# Integrators_Soldier.net
KiCad netlist of a schematic drawn in Altium Designer
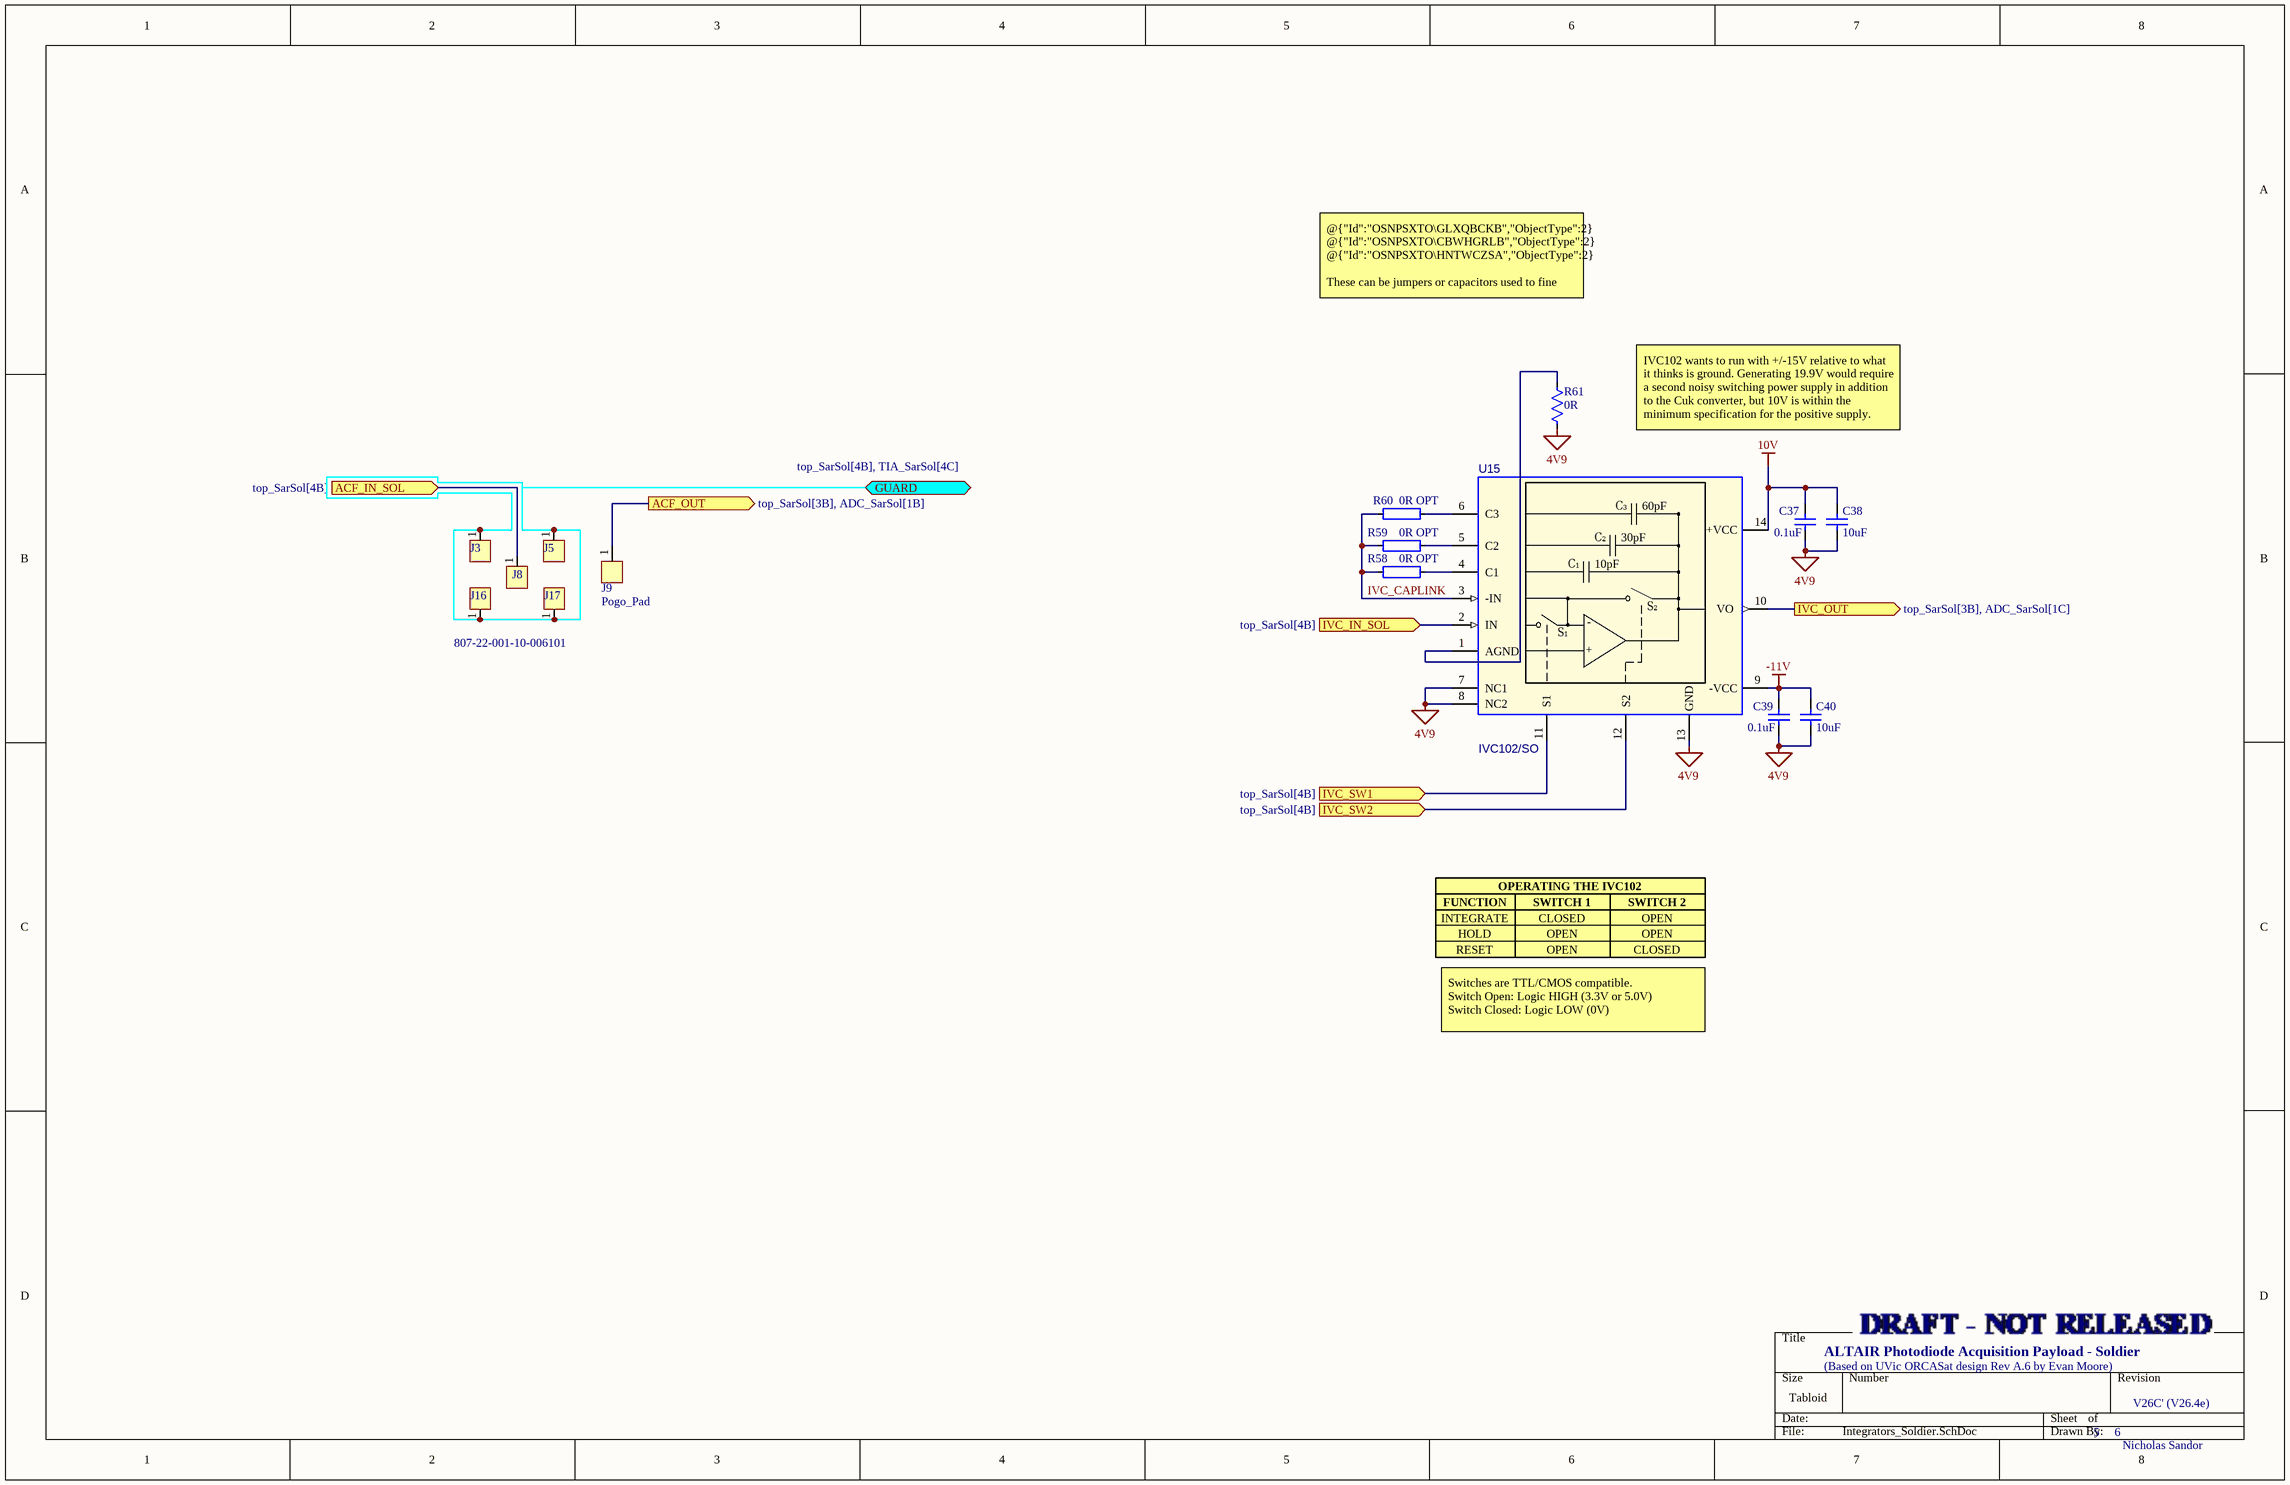
[diagram p0: Integrators_Soldier.SchDoc]

(export (version "E")
  (design (tool "Eeschema 10.0.6"))
  (components
    (comp (ref "C37")
      (value "0.1uF")
      (footprint "CAP 0603 NON-IPC KEMET X7R")
      (description "Kemet C0603C104K5RACAUTO - Cap Ceramic 0.1uF 50V X7R 10% 0603 125C Paper T/R")
      (fields (field (name "MF") "Kemet") (field (name "MP") "C0603C104K5RACAUTO"))
      (libsource (lib "ALTAIR_PD_Capacitors") (part "CAP"))
    )
    (comp (ref "C38")
      (value "10uF")
      (footprint "CAP 0805 IPC MID DENSITY")
      (description "Murata GRM21BR61E106KA73L - Cap Ceramic 10uF 10% 25V X5R 0805")
      (fields (field (name "MF") "Murata") (field (name "MP") "GRM21BR61E106KA73L"))
      (libsource (lib "ALTAIR_PD_Capacitors") (part "CAP"))
    )
    (comp (ref "C39")
      (value "0.1uF")
      (footprint "CAP 0603 NON-IPC KEMET X7R")
      (description "Kemet C0603C104K5RACAUTO - Cap Ceramic 0.1uF 50V X7R 10% 0603 125C Paper T/R")
      (fields (field (name "MF") "Kemet") (field (name "MP") "C0603C104K5RACAUTO"))
      (libsource (lib "ALTAIR_PD_Capacitors") (part "CAP"))
    )
    (comp (ref "C40")
      (value "10uF")
      (footprint "CAP 0805 IPC MID DENSITY")
      (description "Murata GRM21BR61E106KA73L - Cap Ceramic 10uF 10% 25V X5R 0805")
      (fields (field (name "MF") "Murata") (field (name "MP") "GRM21BR61E106KA73L"))
      (libsource (lib "ALTAIR_PD_Capacitors") (part "CAP"))
    )
    (comp (ref "J3")
      (value "807-22-001-10-006101")
      (footprint "POGO PIN 807-22-001-10-006101")
      (description "Mill-Max Individual Insulated Pin 5.99mm Initial Height")
      (fields (field (name "MF") "Mill-Max"))
      (libsource (lib "ALTAIR_PD_Pogo") (part "807-22-001-10-006101"))
    )
    (comp (ref "J5")
      (value "807-22-001-10-006101")
      (footprint "POGO PIN 807-22-001-10-006101")
      (description "Mill-Max Individual Insulated Pin 5.99mm Initial Height")
      (fields (field (name "MF") "Mill-Max"))
      (libsource (lib "ALTAIR_PD_Pogo") (part "807-22-001-10-006101"))
    )
    (comp (ref "J8")
      (value "807-22-001-10-006101")
      (footprint "POGO PIN 807-22-001-10-006101")
      (description "Mill-Max Individual Insulated Pin 5.99mm Initial Height")
      (fields (field (name "MF") "Mill-Max"))
      (libsource (lib "ALTAIR_PD_Pogo") (part "807-22-001-10-006101"))
    )
    (comp (ref "J9")
      (value "Pogo_Pad")
      (footprint "POGO PAD SOLDIER")
      (description "Pad for Pogo Pin without Guard")
      (libsource (lib "ALTAIR_PD_Pogo") (part "Pogo_Pad_NoGuard"))
    )
    (comp (ref "J16")
      (value "807-22-001-10-006101")
      (footprint "POGO PIN 807-22-001-10-006101")
      (description "Mill-Max Individual Insulated Pin 5.99mm Initial Height")
      (fields (field (name "MF") "Mill-Max"))
      (libsource (lib "") (part "807-22-001-10-006101_1"))
    )
    (comp (ref "J17")
      (value "807-22-001-10-006101")
      (footprint "POGO PIN 807-22-001-10-006101")
      (description "Mill-Max Individual Insulated Pin 5.99mm Initial Height")
      (fields (field (name "MF") "Mill-Max"))
      (libsource (lib "") (part "807-22-001-10-006101_1"))
    )
    (comp (ref "R58")
      (value "0R OPT")
      (footprint "RES 0402 IPC LOW DENSITY")
      (description "Yageo RC0402JR-070RL - Res 0 Ohms 1/16W SMD 0402")
      (fields (field (name "MF") "YAGEO") (field (name "MP") "RC0402JR-070RL"))
      (libsource (lib "ALTAIR_PD_Resistors") (part "IMPEDANCE"))
    )
    (comp (ref "R59")
      (value "0R OPT")
      (footprint "RES 0402 IPC LOW DENSITY")
      (description "Yageo RC0402JR-070RL - Res 0 Ohms 1/16W SMD 0402")
      (fields (field (name "MF") "YAGEO") (field (name "MP") "RC0402JR-070RL"))
      (libsource (lib "ALTAIR_PD_Resistors") (part "IMPEDANCE"))
    )
    (comp (ref "R60")
      (value "0R OPT")
      (footprint "RES 0402 IPC LOW DENSITY")
      (description "Yageo RC0402JR-070RL - Res 0 Ohms 1/16W SMD 0402")
      (fields (field (name "MF") "YAGEO") (field (name "MP") "RC0402JR-070RL"))
      (libsource (lib "ALTAIR_PD_Resistors") (part "IMPEDANCE"))
    )
    (comp (ref "R61")
      (value "0R")
      (footprint "RES 0402 IPC MID DENSITY")
      (description "Yageo RC0402JR-070RL - Res 0 Ohms 1/16W SMD 0402")
      (fields (field (name "MF") "YAGEO") (field (name "MP") "RC0402JR-070RL"))
      (libsource (lib "ALTAIR_PD_Resistors") (part "RES"))
    )
    (comp (ref "U15")
      (value "IVC102/SO")
      (footprint "14-SOIC 4MM WIDE LOW DENSITY")
      (description "Precision Switched Integrator Transimpedance Amplifier")
      (fields (field (name "MF") "Texas Instruments") (field (name "MP") "IVC102U"))
      (libsource (lib "ALTAIR_PD_Amplifiers") (part "IVC102/SO_5"))
    )
  )
  (nets
    (net (code "1") (name "-11V") (class "Default")
      (node (ref "C39") (pin "2") (pinfunction "2_2") (pintype "passive"))
      (node (ref "C40") (pin "2") (pinfunction "2_2") (pintype "passive"))
      (node (ref "U15") (pin "9") (pinfunction "-VCC_9") (pintype "power_in"))
    )
    (net (code "2") (name "/ACF_IN_SOL") (class "Default")
      (node (ref "J8") (pin "1") (pinfunction "1_1") (pintype "passive"))
    )
    (net (code "3") (name "/ACF_OUT") (class "Default")
      (node (ref "J9") (pin "1") (pinfunction "1_1") (pintype "passive"))
    )
    (net (code "4") (name "/GUARD") (class "Default")
      (node (ref "J16") (pin "1") (pinfunction "1_1") (pintype "passive"))
      (node (ref "J17") (pin "1") (pinfunction "1_1") (pintype "passive"))
      (node (ref "J3") (pin "1") (pinfunction "1_1") (pintype "passive"))
      (node (ref "J5") (pin "1") (pinfunction "1_1") (pintype "passive"))
    )
    (net (code "5") (name "/IVC_CAPLINK") (class "Default")
      (node (ref "R58") (pin "1") (pinfunction "1_1") (pintype "passive"))
      (node (ref "R59") (pin "1") (pinfunction "1_1") (pintype "passive"))
      (node (ref "R60") (pin "1") (pinfunction "1_1") (pintype "passive"))
      (node (ref "U15") (pin "3") (pinfunction "-IN_3") (pintype "input"))
    )
    (net (code "6") (name "/IVC_IN_SOL") (class "Default")
      (node (ref "U15") (pin "2") (pinfunction "IN_2") (pintype "input"))
    )
    (net (code "7") (name "/IVC_OUT") (class "Default")
      (node (ref "U15") (pin "10") (pinfunction "VO_10") (pintype "output"))
    )
    (net (code "8") (name "/IVC_SW1") (class "Default")
      (node (ref "U15") (pin "11") (pinfunction "S1_11") (pintype "passive"))
    )
    (net (code "9") (name "/IVC_SW2") (class "Default")
      (node (ref "U15") (pin "12") (pinfunction "S2_12") (pintype "passive"))
    )
    (net (code "10") (name "4V9") (class "Default")
      (node (ref "C37") (pin "1") (pinfunction "1_1") (pintype "passive"))
      (node (ref "C38") (pin "1") (pinfunction "1_1") (pintype "passive"))
      (node (ref "C39") (pin "1") (pinfunction "1_1") (pintype "passive"))
      (node (ref "C40") (pin "1") (pinfunction "1_1") (pintype "passive"))
      (node (ref "R61") (pin "2") (pinfunction "2_2") (pintype "passive"))
      (node (ref "U15") (pin "13") (pinfunction "GND_13") (pintype "power_in"))
      (node (ref "U15") (pin "7") (pinfunction "NC1_7") (pintype "passive"))
      (node (ref "U15") (pin "8") (pinfunction "NC2_8") (pintype "passive"))
    )
    (net (code "11") (name "10V") (class "Default")
      (node (ref "C37") (pin "2") (pinfunction "2_2") (pintype "passive"))
      (node (ref "C38") (pin "2") (pinfunction "2_2") (pintype "passive"))
      (node (ref "U15") (pin "14") (pinfunction "+VCC_14") (pintype "power_in"))
    )
    (net (code "12") (name "Net-(U15-AGND)") (class "Default")
      (node (ref "R61") (pin "1") (pinfunction "1_1") (pintype "passive"))
      (node (ref "U15") (pin "1") (pinfunction "AGND_1") (pintype "power_in"))
    )
    (net (code "13") (name "Net-(U15-C1)") (class "Default")
      (node (ref "R58") (pin "2") (pinfunction "2_2") (pintype "passive"))
      (node (ref "U15") (pin "4") (pinfunction "C1_4") (pintype "passive"))
    )
    (net (code "14") (name "Net-(U15-C2)") (class "Default")
      (node (ref "R59") (pin "2") (pinfunction "2_2") (pintype "passive"))
      (node (ref "U15") (pin "5") (pinfunction "C2_5") (pintype "passive"))
    )
    (net (code "15") (name "Net-(U15-C3)") (class "Default")
      (node (ref "R60") (pin "2") (pinfunction "2_2") (pintype "passive"))
      (node (ref "U15") (pin "6") (pinfunction "C3_6") (pintype "passive"))
    )
  )
)
